# 06_BLUETOOTH.net
KiCad netlist of a schematic drawn in Altium Designer
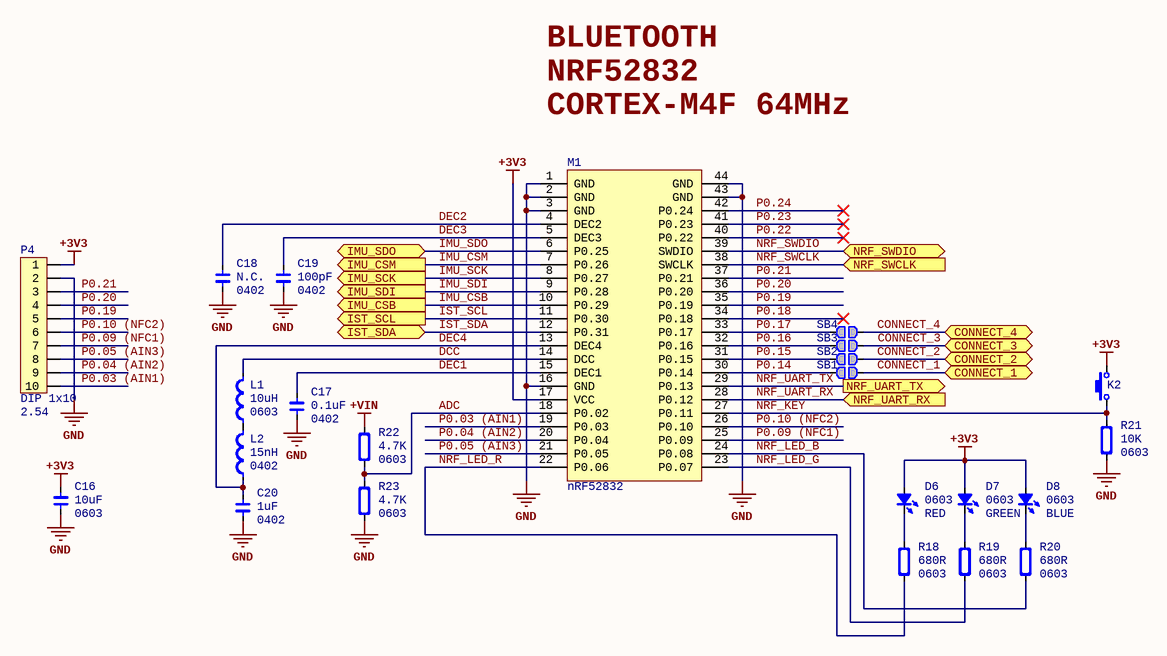
[diagram p0: [06] BLUETOOTH.SchDoc]

(export (version "E")
  (design (tool "Eeschema 10.0.6"))
  (components
    (comp (ref "C16")
      (value "10uF")
      (footprint "PCB_PassiveCap:CAP_0603")
      (description "Capacitor")
      (fields (field (name "TYPE") "0603"))
      (libsource (lib "SCH_Passive") (part "Cap_0603"))
    )
    (comp (ref "C17")
      (value "0.1uF")
      (footprint "PCB_PassiveCap:CAP_0402")
      (description "Capacitor")
      (fields (field (name "TYPE") "0402"))
      (libsource (lib "SCH_Passive") (part "Cap_0402"))
    )
    (comp (ref "C18")
      (value "N.C.")
      (footprint "PCB_PassiveCap:CAP_0402")
      (description "Capacitor")
      (fields (field (name "TYPE") "0402"))
      (libsource (lib "SCH_Passive") (part "Cap_0402"))
    )
    (comp (ref "C19")
      (value "100pF")
      (footprint "PCB_PassiveCap:CAP_0402")
      (description "Capacitor")
      (fields (field (name "TYPE") "0402"))
      (libsource (lib "SCH_Passive") (part "Cap_0402"))
    )
    (comp (ref "C20")
      (value "1uF")
      (footprint "PCB_PassiveCap:CAP_0402")
      (description "Capacitor")
      (fields (field (name "TYPE") "0402"))
      (libsource (lib "SCH_Passive") (part "Cap_0402"))
    )
    (comp (ref "D6")
      (value "RED")
      (footprint "PCB_ActiveLED:LED_0603_RED")
      (description "LED")
      (fields (field (name "TYPE") "0603"))
      (libsource (lib "SCH_Active") (part "LED_0603"))
    )
    (comp (ref "D7")
      (value "GREEN")
      (footprint "PCB_ActiveLED:LED_0603_GREEN")
      (description "LED")
      (fields (field (name "TYPE") "0603"))
      (libsource (lib "SCH_Active") (part "LED_0603"))
    )
    (comp (ref "D8")
      (value "BLUE")
      (footprint "PCB_ActiveLED:LED_0603_BLUE")
      (description "LED")
      (fields (field (name "TYPE") "0603"))
      (libsource (lib "SCH_Active") (part "LED_0603"))
    )
    (comp (ref "K2")
      (value "ButtonTACT")
      (footprint "PCB_Switch:ButtonTACT_3x4x2_180H")
      (description "Button")
      (libsource (lib "SCH_Switch") (part "ButtonTACT_3x4x2_180"))
    )
    (comp (ref "L1")
      (value "10uH")
      (footprint "PCB_PassiveInd:IND_0603")
      (description "Inductor")
      (fields (field (name "TYPE") "0603"))
      (libsource (lib "SCH_Passive") (part "Ind_0603"))
    )
    (comp (ref "L2")
      (value "15nH")
      (footprint "PCB_PassiveInd:IND_0402")
      (description "Inductor")
      (fields (field (name "TYPE") "0402"))
      (libsource (lib "SCH_Passive") (part "Ind_0402"))
    )
    (comp (ref "M1")
      (value "nRF52832")
      (footprint "PCB_Module:E73-2G4M04S")
      (description "Module")
      (fields (field (name "Comment") "BT_E73-2G4M04S"))
      (libsource (lib "SCH_Module") (part "BT_E73-2G4M04S"))
    )
    (comp (ref "P4")
      (value "2.54")
      (footprint "PCB_ConnectorHDR:HDR1X10_2.54_180")
      (description "Header")
      (fields (field (name "TYPE") "DIP 1x10") (field (name "Comment") "DIP 1x10"))
      (libsource (lib "SCH_ConnectorHDR") (part "HDR1x10_2.54T"))
    )
    (comp (ref "R18")
      (value "680R")
      (footprint "PCB_PassiveRes:RES_0603")
      (description "Resistor")
      (fields (field (name "TYPE") "0603"))
      (libsource (lib "SCH_Passive") (part "Res_0603"))
    )
    (comp (ref "R19")
      (value "680R")
      (footprint "PCB_PassiveRes:RES_0603")
      (description "Resistor")
      (fields (field (name "TYPE") "0603"))
      (libsource (lib "SCH_Passive") (part "Res_0603"))
    )
    (comp (ref "R20")
      (value "680R")
      (footprint "PCB_PassiveRes:RES_0603")
      (description "Resistor")
      (fields (field (name "TYPE") "0603"))
      (libsource (lib "SCH_Passive") (part "Res_0603"))
    )
    (comp (ref "R21")
      (value "10K")
      (footprint "PCB_PassiveRes:RES_0603")
      (description "Resistor")
      (fields (field (name "TYPE") "0603"))
      (libsource (lib "SCH_Passive") (part "Res_0603"))
    )
    (comp (ref "R22")
      (value "4.7K")
      (footprint "PCB_PassiveRes:RES_0603")
      (description "Resistor")
      (fields (field (name "TYPE") "0603"))
      (libsource (lib "SCH_Passive") (part "Res_0603"))
    )
    (comp (ref "R23")
      (value "4.7K")
      (footprint "PCB_PassiveRes:RES_0603")
      (description "Resistor")
      (fields (field (name "TYPE") "0603"))
      (libsource (lib "SCH_Passive") (part "Res_0603"))
    )
    (comp (ref "SB1")
      (value "Solderbridge")
      (footprint "PCB_Mechanical:Solderbridge")
      (libsource (lib "SCH_Mechanical") (part "Solderbridge"))
    )
    (comp (ref "SB2")
      (value "Solderbridge")
      (footprint "PCB_Mechanical:Solderbridge")
      (libsource (lib "SCH_Mechanical") (part "Solderbridge"))
    )
    (comp (ref "SB3")
      (value "Solderbridge")
      (footprint "PCB_Mechanical:Solderbridge")
      (libsource (lib "SCH_Mechanical") (part "Solderbridge"))
    )
    (comp (ref "SB4")
      (value "Solderbridge")
      (footprint "PCB_Mechanical:Solderbridge")
      (libsource (lib "SCH_Mechanical") (part "Solderbridge"))
    )
  )
  (nets
    (net (code "1") (name "+3V3") (class "Default")
      (node (ref "C16") (pin "2") (pinfunction "2_2") (pintype "passive"))
      (node (ref "D6") (pin "1") (pinfunction "A_1") (pintype "passive"))
      (node (ref "D7") (pin "1") (pinfunction "A_1") (pintype "passive"))
      (node (ref "D8") (pin "1") (pinfunction "A_1") (pintype "passive"))
      (node (ref "K2") (pin "2") (pinfunction "2_2") (pintype "passive"))
      (node (ref "M1") (pin "17") (pinfunction "VCC_17") (pintype "passive"))
      (node (ref "P4") (pin "1") (pinfunction "1_1") (pintype "passive"))
    )
    (net (code "2") (name "+VIN") (class "Default")
      (node (ref "R22") (pin "2") (pinfunction "2_2") (pintype "passive"))
    )
    (net (code "3") (name "/ADC") (class "Default")
      (node (ref "M1") (pin "18") (pinfunction "P0.02_18") (pintype "passive"))
      (node (ref "R22") (pin "1") (pinfunction "1_1") (pintype "passive"))
      (node (ref "R23") (pin "2") (pinfunction "2_2") (pintype "passive"))
    )
    (net (code "4") (name "/CONNECT_1") (class "Default")
      (node (ref "SB1") (pin "2") (pinfunction "2_2") (pintype "passive"))
    )
    (net (code "5") (name "/CONNECT_2") (class "Default")
      (node (ref "SB2") (pin "2") (pinfunction "2_2") (pintype "passive"))
    )
    (net (code "6") (name "/CONNECT_3") (class "Default")
      (node (ref "SB3") (pin "2") (pinfunction "2_2") (pintype "passive"))
    )
    (net (code "7") (name "/CONNECT_4") (class "Default")
      (node (ref "SB4") (pin "2") (pinfunction "2_2") (pintype "passive"))
    )
    (net (code "8") (name "/DCC") (class "Default")
      (node (ref "L1") (pin "2") (pinfunction "2_2") (pintype "passive"))
      (node (ref "M1") (pin "14") (pinfunction "DCC_14") (pintype "passive"))
    )
    (net (code "9") (name "/DEC1") (class "Default")
      (node (ref "C17") (pin "2") (pinfunction "2_2") (pintype "passive"))
      (node (ref "M1") (pin "15") (pinfunction "DEC1_15") (pintype "passive"))
    )
    (net (code "10") (name "/DEC2") (class "Default")
      (node (ref "C18") (pin "2") (pinfunction "2_2") (pintype "passive"))
      (node (ref "M1") (pin "4") (pinfunction "DEC2_4") (pintype "passive"))
    )
    (net (code "11") (name "/DEC3") (class "Default")
      (node (ref "C19") (pin "2") (pinfunction "2_2") (pintype "passive"))
      (node (ref "M1") (pin "5") (pinfunction "DEC3_5") (pintype "passive"))
    )
    (net (code "12") (name "/DEC4") (class "Default")
      (node (ref "C20") (pin "2") (pinfunction "2_2") (pintype "passive"))
      (node (ref "L2") (pin "1") (pinfunction "1_1") (pintype "passive"))
      (node (ref "M1") (pin "13") (pinfunction "DEC4_13") (pintype "passive"))
    )
    (net (code "13") (name "/IMU_CSB") (class "Default")
      (node (ref "M1") (pin "10") (pinfunction "P0.29_10") (pintype "passive"))
    )
    (net (code "14") (name "/IMU_CSM") (class "Default")
      (node (ref "M1") (pin "7") (pinfunction "P0.26_7") (pintype "passive"))
    )
    (net (code "15") (name "/IMU_SCK") (class "Default")
      (node (ref "M1") (pin "8") (pinfunction "P0.27_8") (pintype "passive"))
    )
    (net (code "16") (name "/IMU_SDI") (class "Default")
      (node (ref "M1") (pin "9") (pinfunction "P0.28_9") (pintype "passive"))
    )
    (net (code "17") (name "/IMU_SDO") (class "Default")
      (node (ref "M1") (pin "6") (pinfunction "P0.25_6") (pintype "passive"))
    )
    (net (code "18") (name "/IST_SCL") (class "Default")
      (node (ref "M1") (pin "11") (pinfunction "P0.30_11") (pintype "passive"))
    )
    (net (code "19") (name "/IST_SDA") (class "Default")
      (node (ref "M1") (pin "12") (pinfunction "P0.31_12") (pintype "passive"))
    )
    (net (code "20") (name "/NRF_KEY") (class "Default")
      (node (ref "K2") (pin "1") (pinfunction "1_1") (pintype "passive"))
      (node (ref "M1") (pin "27") (pinfunction "P0.11_27") (pintype "passive"))
      (node (ref "R21") (pin "2") (pinfunction "2_2") (pintype "passive"))
    )
    (net (code "21") (name "/NRF_LED_B") (class "Default")
      (node (ref "M1") (pin "24") (pinfunction "P0.08_24") (pintype "passive"))
      (node (ref "R20") (pin "1") (pinfunction "1_1") (pintype "passive"))
    )
    (net (code "22") (name "/NRF_LED_G") (class "Default")
      (node (ref "M1") (pin "23") (pinfunction "P0.07_23") (pintype "passive"))
      (node (ref "R19") (pin "1") (pinfunction "1_1") (pintype "passive"))
    )
    (net (code "23") (name "/NRF_LED_R") (class "Default")
      (node (ref "M1") (pin "22") (pinfunction "P0.06_22") (pintype "passive"))
      (node (ref "R18") (pin "1") (pinfunction "1_1") (pintype "passive"))
    )
    (net (code "24") (name "/NRF_SWCLK") (class "Default")
      (node (ref "M1") (pin "38") (pinfunction "SWCLK_38") (pintype "passive"))
    )
    (net (code "25") (name "/NRF_SWDIO") (class "Default")
      (node (ref "M1") (pin "39") (pinfunction "SWDIO_39") (pintype "passive"))
    )
    (net (code "26") (name "/NRF_UART_RX") (class "Default")
      (node (ref "M1") (pin "28") (pinfunction "P0.12_28") (pintype "passive"))
    )
    (net (code "27") (name "/NRF_UART_TX") (class "Default")
      (node (ref "M1") (pin "29") (pinfunction "P0.13_29") (pintype "passive"))
    )
    (net (code "28") (name "/P0.03 (AIN1)") (class "Default")
      (node (ref "M1") (pin "19") (pinfunction "P0.03_19") (pintype "passive"))
      (node (ref "P4") (pin "10") (pinfunction "10_10") (pintype "passive"))
    )
    (net (code "29") (name "/P0.04 (AIN2)") (class "Default")
      (node (ref "M1") (pin "20") (pinfunction "P0.04_20") (pintype "passive"))
      (node (ref "P4") (pin "9") (pinfunction "9_9") (pintype "passive"))
    )
    (net (code "30") (name "/P0.05 (AIN3)") (class "Default")
      (node (ref "M1") (pin "21") (pinfunction "P0.05_21") (pintype "passive"))
      (node (ref "P4") (pin "8") (pinfunction "8_8") (pintype "passive"))
    )
    (net (code "31") (name "/P0.09 (NFC1)") (class "Default")
      (node (ref "M1") (pin "25") (pinfunction "P0.09_25") (pintype "passive"))
      (node (ref "P4") (pin "7") (pinfunction "7_7") (pintype "passive"))
    )
    (net (code "32") (name "/P0.10 (NFC2)") (class "Default")
      (node (ref "M1") (pin "26") (pinfunction "P0.10_26") (pintype "passive"))
      (node (ref "P4") (pin "6") (pinfunction "6_6") (pintype "passive"))
    )
    (net (code "33") (name "/P0.14") (class "Default")
      (node (ref "M1") (pin "30") (pinfunction "P0.14_30") (pintype "passive"))
      (node (ref "SB1") (pin "1") (pinfunction "1_1") (pintype "passive"))
    )
    (net (code "34") (name "/P0.15") (class "Default")
      (node (ref "M1") (pin "31") (pinfunction "P0.15_31") (pintype "passive"))
      (node (ref "SB2") (pin "1") (pinfunction "1_1") (pintype "passive"))
    )
    (net (code "35") (name "/P0.16") (class "Default")
      (node (ref "M1") (pin "32") (pinfunction "P0.16_32") (pintype "passive"))
      (node (ref "SB3") (pin "1") (pinfunction "1_1") (pintype "passive"))
    )
    (net (code "36") (name "/P0.17") (class "Default")
      (node (ref "M1") (pin "33") (pinfunction "P0.17_33") (pintype "passive"))
      (node (ref "SB4") (pin "1") (pinfunction "1_1") (pintype "passive"))
    )
    (net (code "37") (name "/P0.18") (class "Default")
      (node (ref "M1") (pin "34") (pinfunction "P0.18_34") (pintype "passive+no_connect"))
    )
    (net (code "38") (name "/P0.19") (class "Default")
      (node (ref "M1") (pin "35") (pinfunction "P0.19_35") (pintype "passive"))
      (node (ref "P4") (pin "5") (pinfunction "5_5") (pintype "passive"))
    )
    (net (code "39") (name "/P0.20") (class "Default")
      (node (ref "M1") (pin "36") (pinfunction "P0.20_36") (pintype "passive"))
      (node (ref "P4") (pin "4") (pinfunction "4_4") (pintype "passive"))
    )
    (net (code "40") (name "/P0.21") (class "Default")
      (node (ref "M1") (pin "37") (pinfunction "P0.21_37") (pintype "passive"))
      (node (ref "P4") (pin "3") (pinfunction "3_3") (pintype "passive"))
    )
    (net (code "41") (name "/P0.22") (class "Default")
      (node (ref "M1") (pin "40") (pinfunction "P0.22_40") (pintype "passive+no_connect"))
    )
    (net (code "42") (name "/P0.23") (class "Default")
      (node (ref "M1") (pin "41") (pinfunction "P0.23_41") (pintype "passive+no_connect"))
    )
    (net (code "43") (name "/P0.24") (class "Default")
      (node (ref "M1") (pin "42") (pinfunction "P0.24_42") (pintype "passive+no_connect"))
    )
    (net (code "44") (name "GND") (class "Default")
      (node (ref "C16") (pin "1") (pinfunction "1_1") (pintype "passive"))
      (node (ref "C17") (pin "1") (pinfunction "1_1") (pintype "passive"))
      (node (ref "C18") (pin "1") (pinfunction "1_1") (pintype "passive"))
      (node (ref "C19") (pin "1") (pinfunction "1_1") (pintype "passive"))
      (node (ref "C20") (pin "1") (pinfunction "1_1") (pintype "passive"))
      (node (ref "M1") (pin "1") (pinfunction "GND_1") (pintype "passive"))
      (node (ref "M1") (pin "16") (pinfunction "GND_16") (pintype "passive"))
      (node (ref "M1") (pin "2") (pinfunction "GND_2") (pintype "passive"))
      (node (ref "M1") (pin "3") (pinfunction "GND_3") (pintype "passive"))
      (node (ref "M1") (pin "43") (pinfunction "GND_43") (pintype "passive"))
      (node (ref "M1") (pin "44") (pinfunction "GND_44") (pintype "passive"))
      (node (ref "P4") (pin "2") (pinfunction "2_2") (pintype "passive"))
      (node (ref "R21") (pin "1") (pinfunction "1_1") (pintype "passive"))
      (node (ref "R23") (pin "1") (pinfunction "1_1") (pintype "passive"))
    )
    (net (code "45") (name "Net-(D6-K)") (class "Default")
      (node (ref "D6") (pin "2") (pinfunction "K_2") (pintype "passive"))
      (node (ref "R18") (pin "2") (pinfunction "2_2") (pintype "passive"))
    )
    (net (code "46") (name "Net-(D7-K)") (class "Default")
      (node (ref "D7") (pin "2") (pinfunction "K_2") (pintype "passive"))
      (node (ref "R19") (pin "2") (pinfunction "2_2") (pintype "passive"))
    )
    (net (code "47") (name "Net-(D8-K)") (class "Default")
      (node (ref "D8") (pin "2") (pinfunction "K_2") (pintype "passive"))
      (node (ref "R20") (pin "2") (pinfunction "2_2") (pintype "passive"))
    )
    (net (code "48") (name "Net-(L1-Pad1)") (class "Default")
      (node (ref "L1") (pin "1") (pinfunction "1_1") (pintype "passive"))
      (node (ref "L2") (pin "2") (pinfunction "2_2") (pintype "passive"))
    )
  )
)
